# TC.net
KiCad netlist of a schematic drawn in Altium Designer
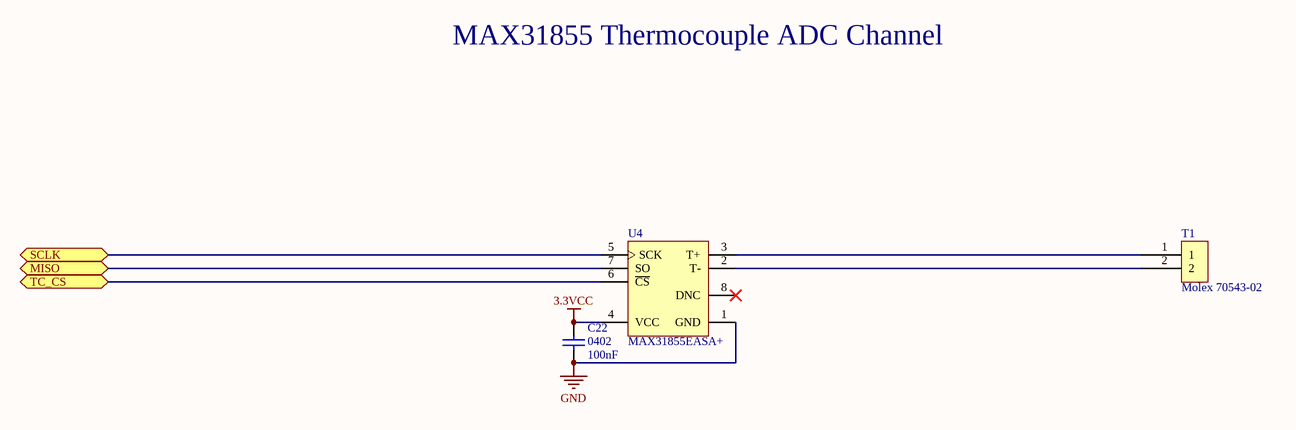
[diagram p0: TC.SchDoc]

(export (version "E")
  (design (tool "Eeschema 10.0.6"))
  (components
    (comp (ref "C22")
      (value "100nF")
      (footprint "C0402")
      (description "Capacitor (Semiconductor SIM Model)")
      (fields
        (field (name "MFR PART #") "GRM155R71C104KA88D")
        (field (name "MFR") "Murata")
        (field (name "PACKAGEREFERENCE") "0402")
        (field (name "PUBLISHER") "Ultimachine")
      )
      (libsource (lib "Tigershark3D") (part "100nF C0402 - GRM155R71C104KA88D"))
    )
    (comp (ref "T1")
      (value "Molex 70543-02")
      (footprint "70543-02")
      (libsource (lib "ZMBo Schematic Library") (part "Molex 70543-02"))
    )
    (comp (ref "U4")
      (value "MAX31855EASA+")
      (footprint "MAXM-S8+4_N")
      (fields (field (name "GENERIC PART NUMBER") "MAX31855"))
      (libsource (lib "Maxim Sensors") (part "MAX31855EASA+"))
    )
  )
  (nets
    (net (code "1") (name "/MISO") (class "Default")
      (node (ref "U4") (pin "7") (pinfunction "SO_7") (pintype "passive"))
    )
    (net (code "2") (name "/SCLK") (class "Default")
      (node (ref "U4") (pin "5") (pinfunction "SCK_5") (pintype "passive"))
    )
    (net (code "3") (name "/TC_CS") (class "Default")
      (node (ref "U4") (pin "6") (pinfunction "~{CS}_6") (pintype "passive"))
    )
    (net (code "4") (name "3.3VCC") (class "Default")
      (node (ref "C22") (pin "2") (pinfunction "2_2") (pintype "passive"))
      (node (ref "U4") (pin "4") (pinfunction "VCC_4") (pintype "power_in"))
    )
    (net (code "5") (name "GND") (class "Default")
      (node (ref "C22") (pin "1") (pinfunction "1_1") (pintype "passive"))
      (node (ref "U4") (pin "1") (pinfunction "GND_1") (pintype "passive"))
    )
    (net (code "6") (name "Net-(U4-T+)") (class "Default")
      (node (ref "T1") (pin "1") (pinfunction "1_1") (pintype "passive"))
      (node (ref "U4") (pin "3") (pinfunction "T+_3") (pintype "passive"))
    )
    (net (code "7") (name "Net-(U4-T-)") (class "Default")
      (node (ref "T1") (pin "2") (pinfunction "2_2") (pintype "passive"))
      (node (ref "U4") (pin "2") (pinfunction "T-_2") (pintype "passive"))
    )
    (net (code "8") (name "unconnected-(U4-DNC-Pad8)") (class "Default")
      (node (ref "U4") (pin "8") (pinfunction "DNC_8") (pintype "passive+no_connect"))
    )
  )
)
